# ItsyBitsy_Expander_v2_1_RP2040.net
KiCad netlist of a schematic drawn in EAGLE
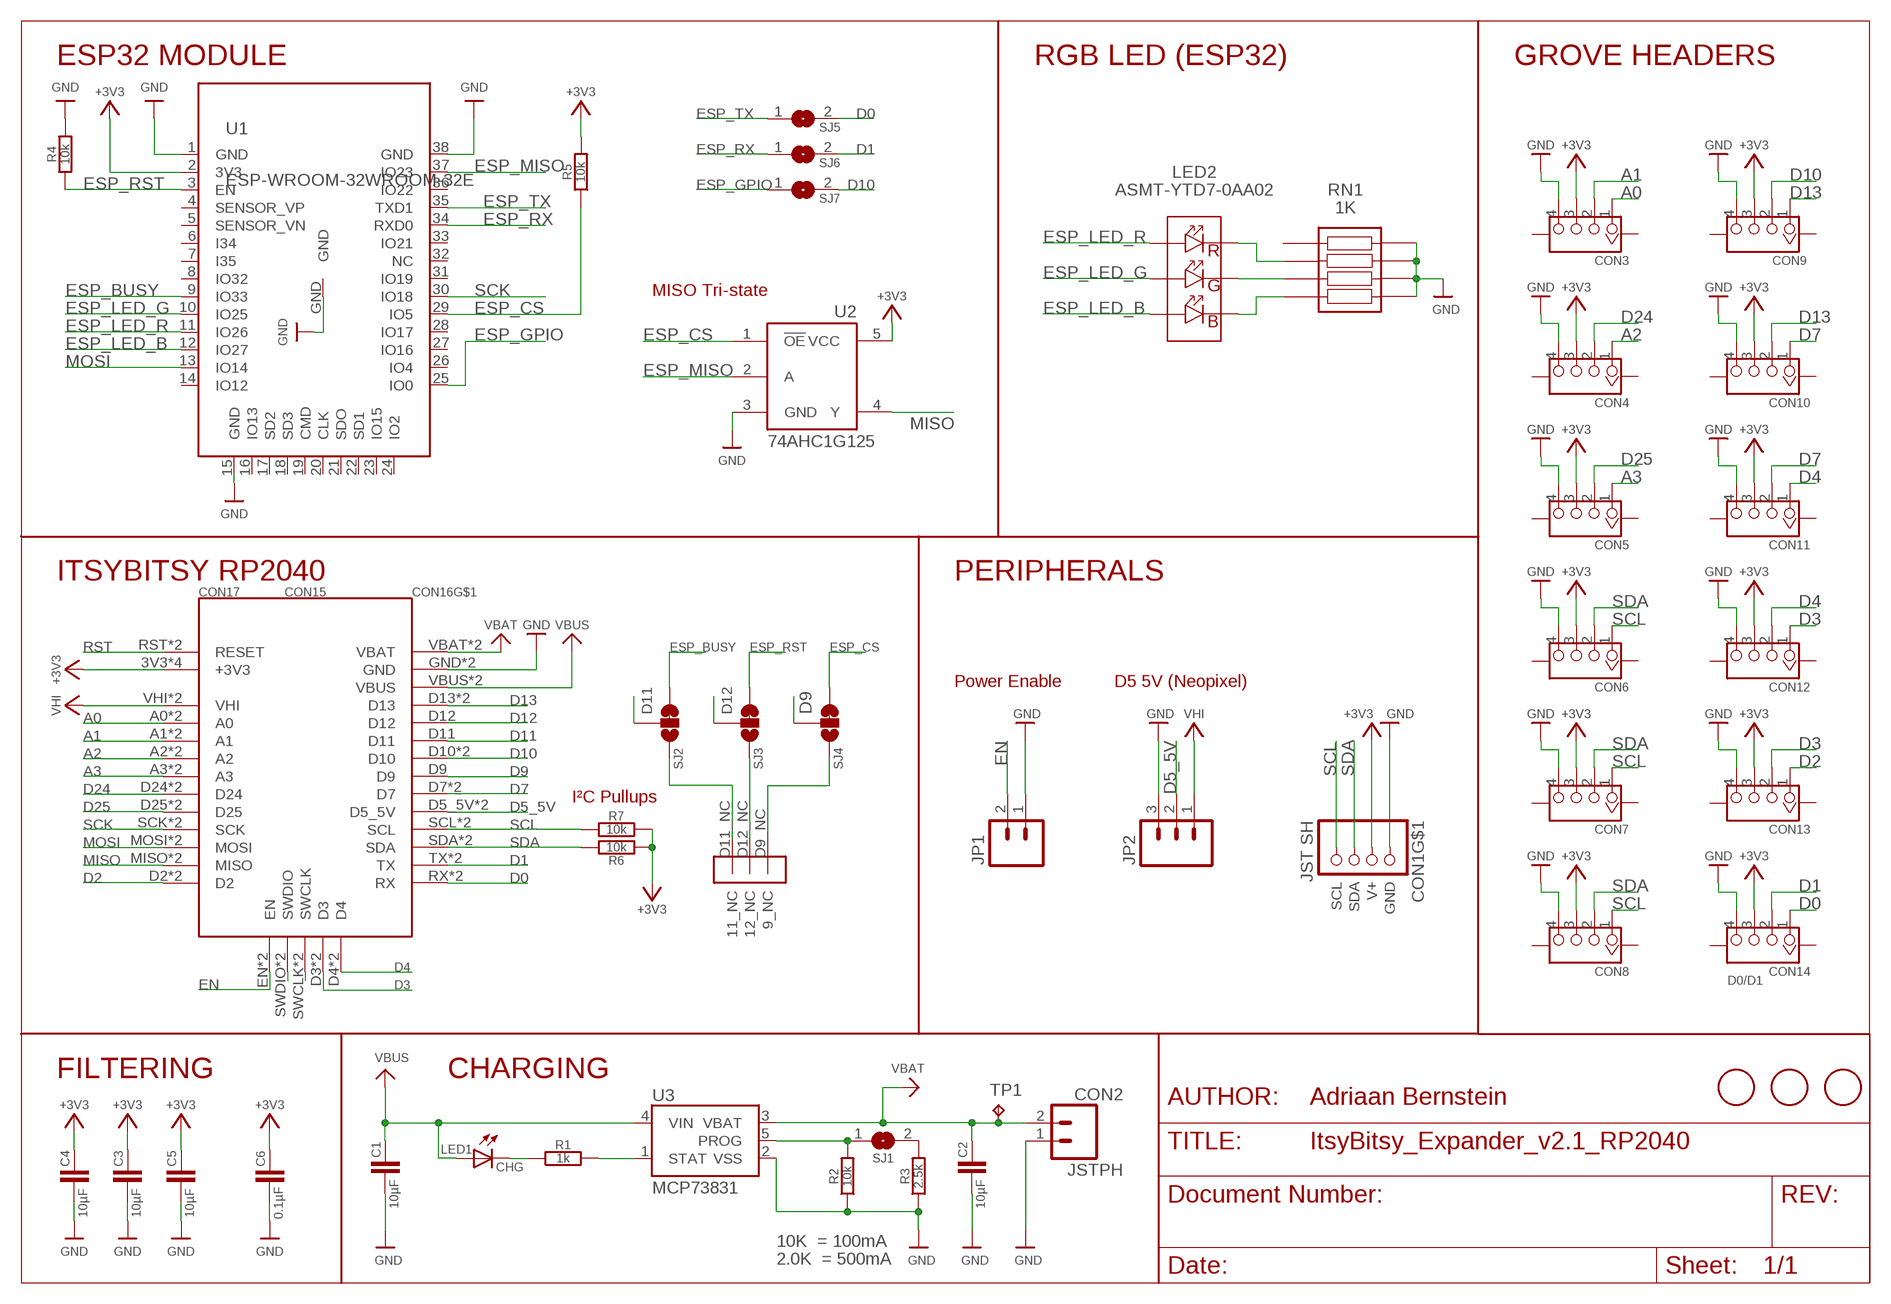
[diagram p0: schematic, sheet 1]

(export (version "E")
  (design (tool "Eeschema 10.0.6"))
  (components
    (comp (ref "C1")
      (value "10µF")
      (footprint "eagle-import:C0805")
      (libsource (lib "eagle-import") (part "C-EUC0805"))
    )
    (comp (ref "C2")
      (value "10µF")
      (footprint "eagle-import:C0805")
      (libsource (lib "eagle-import") (part "C-EUC0805"))
    )
    (comp (ref "C3")
      (value "10µF")
      (footprint "eagle-import:C0805")
      (libsource (lib "eagle-import") (part "C-EUC0805"))
    )
    (comp (ref "C4")
      (value "10µF")
      (footprint "eagle-import:C0805")
      (libsource (lib "eagle-import") (part "C-EUC0805"))
    )
    (comp (ref "C5")
      (value "10µF")
      (footprint "eagle-import:C0805")
      (libsource (lib "eagle-import") (part "C-EUC0805"))
    )
    (comp (ref "C6")
      (value "0.1µF")
      (footprint "eagle-import:C0805")
      (libsource (lib "eagle-import") (part "C-EUC0805"))
    )
    (comp (ref "CON1")
      (value "JST SH")
      (footprint "eagle-import:JST_SH4")
      (libsource (lib "eagle-import") (part "STEMMA_I2C_QT"))
    )
    (comp (ref "CON2")
      (value "JSTPH")
      (footprint "eagle-import:JST-2-SMD")
      (libsource (lib "eagle-import") (part "M02-JST-2MM-SMT"))
    )
    (comp (ref "CON3")
      (value "H4P-SMD-2.0")
      (footprint "eagle-import:HW4-PTH-2.0")
      (libsource (lib "eagle-import") (part "GROVE-CONNECTOR-4PINHW4-PTH-2.0"))
    )
    (comp (ref "CON4")
      (value "H4P-SMD-2.0")
      (footprint "eagle-import:HW4-PTH-2.0")
      (libsource (lib "eagle-import") (part "GROVE-CONNECTOR-4PINHW4-PTH-2.0"))
    )
    (comp (ref "CON5")
      (value "H4P-SMD-2.0")
      (footprint "eagle-import:HW4-PTH-2.0")
      (libsource (lib "eagle-import") (part "GROVE-CONNECTOR-4PINHW4-PTH-2.0"))
    )
    (comp (ref "CON6")
      (value "H4P-SMD-2.0")
      (footprint "eagle-import:HW4-PTH-2.0")
      (libsource (lib "eagle-import") (part "GROVE-CONNECTOR-4PINHW4-PTH-2.0"))
    )
    (comp (ref "CON7")
      (value "H4P-SMD-2.0")
      (footprint "eagle-import:HW4-PTH-2.0")
      (libsource (lib "eagle-import") (part "GROVE-CONNECTOR-4PINHW4-PTH-2.0"))
    )
    (comp (ref "CON8")
      (value "H4P-SMD-2.0")
      (footprint "eagle-import:HW4-PTH-2.0")
      (libsource (lib "eagle-import") (part "GROVE-CONNECTOR-4PINHW4-PTH-2.0"))
    )
    (comp (ref "CON9")
      (value "H4P-SMD-2.0")
      (footprint "eagle-import:HW4-PTH-2.0")
      (libsource (lib "eagle-import") (part "GROVE-CONNECTOR-4PINHW4-PTH-2.0"))
    )
    (comp (ref "CON10")
      (value "H4P-SMD-2.0")
      (footprint "eagle-import:HW4-PTH-2.0")
      (libsource (lib "eagle-import") (part "GROVE-CONNECTOR-4PINHW4-PTH-2.0"))
    )
    (comp (ref "CON11")
      (value "H4P-SMD-2.0")
      (footprint "eagle-import:HW4-PTH-2.0")
      (libsource (lib "eagle-import") (part "GROVE-CONNECTOR-4PINHW4-PTH-2.0"))
    )
    (comp (ref "CON12")
      (value "H4P-SMD-2.0")
      (footprint "eagle-import:HW4-PTH-2.0")
      (libsource (lib "eagle-import") (part "GROVE-CONNECTOR-4PINHW4-PTH-2.0"))
    )
    (comp (ref "CON13")
      (value "H4P-SMD-2.0")
      (footprint "eagle-import:HW4-PTH-2.0")
      (libsource (lib "eagle-import") (part "GROVE-CONNECTOR-4PINHW4-PTH-2.0"))
    )
    (comp (ref "CON14")
      (value "H4P-SMD-2.0")
      (footprint "eagle-import:HW4-PTH-2.0")
      (libsource (lib "eagle-import") (part "GROVE-CONNECTOR-4PINHW4-PTH-2.0"))
    )
    (comp (ref "CON15")
      (value "ITSYBITSY_RP2040_EDGEDEBUG")
      (footprint "eagle-import:ITSYBITSY_RP2040_PTH_EDGEDEBUG")
      (libsource (lib "eagle-import") (part "ITSYBITSY_RP2040_EDGEDEBUG"))
    )
    (comp (ref "CON16")
      (value "ITSYBITSY_RP2040_EDGEGND")
      (footprint "eagle-import:ITSYBITSY_RP2040_SMD_EDGEGND")
      (libsource (lib "eagle-import") (part "ITSYBITSY_RP2040_EDGEGND"))
    )
    (comp (ref "CON17")
      (value "ITSYBITSY_RP2040_EDGEPWR")
      (footprint "eagle-import:ITSYBITSY_RP2040_SMD_EDGEPWR")
      (libsource (lib "eagle-import") (part "ITSYBITSY_RP2040_EDGEPWR"))
    )
    (comp (ref "FD1")
      (value "FIDUCIAL")
      (footprint "eagle-import:FIDUCIAL_1MM")
      (libsource (lib "eagle-import") (part "FIDUCIAL"))
    )
    (comp (ref "FD2")
      (value "FIDUCIAL")
      (footprint "eagle-import:FIDUCIAL_1MM")
      (libsource (lib "eagle-import") (part "FIDUCIAL"))
    )
    (comp (ref "FD3")
      (value "FIDUCIAL")
      (footprint "eagle-import:FIDUCIAL_1MM")
      (libsource (lib "eagle-import") (part "FIDUCIAL"))
    )
    (comp (ref "JP1")
      (value "M02PTH")
      (footprint "eagle-import:1X02")
      (libsource (lib "eagle-import") (part "M02PTH"))
    )
    (comp (ref "JP2")
      (value "M03PTH")
      (footprint "eagle-import:1X03")
      (libsource (lib "eagle-import") (part "M03PTH"))
    )
    (comp (ref "LED1")
      (value "CHG")
      (footprint "eagle-import:CHIP-LED0603")
      (libsource (lib "eagle-import") (part "LEDCHIP-LED0603"))
    )
    (comp (ref "LED2")
      (value "ASMT-YTD7-0AA02")
      (footprint "eagle-import:ASMTYTD70AA02")
      (fields (field (name "MOUSER_PART_NUMBER") "630-ASMT-YTD7-0AA02"))
      (libsource (lib "eagle-import") (part "ASMT-YTD7-0AA02"))
    )
    (comp (ref "R1")
      (value "1k")
      (footprint "eagle-import:R0603")
      (libsource (lib "eagle-import") (part "R-EU_R0603"))
    )
    (comp (ref "R2")
      (value "10k")
      (footprint "eagle-import:R0603")
      (libsource (lib "eagle-import") (part "R-EU_R0603"))
    )
    (comp (ref "R3")
      (value "2.5k")
      (footprint "eagle-import:R0603")
      (libsource (lib "eagle-import") (part "R-EU_R0603"))
    )
    (comp (ref "R4")
      (value "10k")
      (footprint "eagle-import:R0603")
      (libsource (lib "eagle-import") (part "R-EU_R0603"))
    )
    (comp (ref "R5")
      (value "10k")
      (footprint "eagle-import:R0603")
      (libsource (lib "eagle-import") (part "R-EU_R0603"))
    )
    (comp (ref "R6")
      (value "10k")
      (footprint "eagle-import:R0603")
      (libsource (lib "eagle-import") (part "R-EU_R0603"))
    )
    (comp (ref "R7")
      (value "10k")
      (footprint "eagle-import:R0603")
      (libsource (lib "eagle-import") (part "R-EU_R0603"))
    )
    (comp (ref "RN1")
      (value "1K")
      (footprint "eagle-import:CAY1647R0F4LF")
      (fields
        (field (name "MANUFACTURER_PART_NUMBER") "CAY16-221J4AS")
        (field (name "MOUSER_PART_NUMBER") "652-CAY16-221J4AS")
      )
      (libsource (lib "eagle-import") (part "CAY16-221J4AS"))
    )
    (comp (ref "SJ1") (value "SJ") (footprint "eagle-import:SJ") (libsource (lib "eagle-import") (part "SJ")))
    (comp (ref "SJ5") (value "SJ") (footprint "eagle-import:SJ") (libsource (lib "eagle-import") (part "SJ")))
    (comp (ref "SJ6") (value "SJ") (footprint "eagle-import:SJ") (libsource (lib "eagle-import") (part "SJ")))
    (comp (ref "SJ7") (value "SJ") (footprint "eagle-import:SJ") (libsource (lib "eagle-import") (part "SJ")))
    (comp (ref "SJ_D11")
      (value "SJ2")
      (footprint "eagle-import:SJ_2WAY_CLOSED")
      (libsource (lib "eagle-import") (part "SJ_2WAY_CLOSED"))
    )
    (comp (ref "SJ_D12")
      (value "SJ3")
      (footprint "eagle-import:SJ_2WAY_CLOSED")
      (libsource (lib "eagle-import") (part "SJ_2WAY_CLOSED"))
    )
    (comp (ref "SJ_D13")
      (value "SJ4")
      (footprint "eagle-import:SJ_2WAY_CLOSED")
      (libsource (lib "eagle-import") (part "SJ_2WAY_CLOSED"))
    )
    (comp (ref "TP1")
      (value "TPB1,27")
      (footprint "eagle-import:B1,27")
      (libsource (lib "eagle-import") (part "TPB1,27"))
    )
    (comp (ref "U1")
      (value "ESP-WROOM-32WROOM-32E")
      (footprint "eagle-import:ESP-WROOM-32E")
      (libsource (lib "eagle-import") (part "ESP-WROOM-32WROOM-32E"))
    )
    (comp (ref "U2")
      (value "74AHC1G125")
      (footprint "eagle-import:SOT23-5L")
      (libsource (lib "eagle-import") (part "74AHC1G125"))
    )
    (comp (ref "U3")
      (value "MCP73831")
      (footprint "eagle-import:SOT23-5")
      (libsource (lib "eagle-import") (part "MCP73831"))
    )
  )
  (nets
    (net (code "1") (name "+3V3") (class "Default")
      (node (ref "C3") (pin "1") (pinfunction "1_1") (pintype "passive"))
      (node (ref "C4") (pin "1") (pinfunction "1_1") (pintype "passive"))
      (node (ref "C5") (pin "1") (pinfunction "1_1") (pintype "passive"))
      (node (ref "C6") (pin "1") (pinfunction "1_1") (pintype "passive"))
      (node (ref "CON1") (pin "2") (pinfunction "V+_2") (pintype "passive"))
      (node (ref "CON10") (pin "3") (pinfunction "3_3") (pintype "bidirectional"))
      (node (ref "CON11") (pin "3") (pinfunction "3_3") (pintype "bidirectional"))
      (node (ref "CON12") (pin "3") (pinfunction "3_3") (pintype "bidirectional"))
      (node (ref "CON13") (pin "3") (pinfunction "3_3") (pintype "bidirectional"))
      (node (ref "CON14") (pin "3") (pinfunction "3_3") (pintype "bidirectional"))
      (node (ref "CON17") (pin "3V3") (pinfunction "+3V3_3V3") (pintype "bidirectional"))
      (node (ref "CON17") (pin "3V3_2") (pinfunction "+3V3_3V3_2") (pintype "bidirectional"))
      (node (ref "CON17") (pin "3V3_3") (pinfunction "+3V3_3V3_3") (pintype "bidirectional"))
      (node (ref "CON17") (pin "3V3_4") (pinfunction "+3V3_3V3_4") (pintype "bidirectional"))
      (node (ref "CON3") (pin "3") (pinfunction "3_3") (pintype "bidirectional"))
      (node (ref "CON4") (pin "3") (pinfunction "3_3") (pintype "bidirectional"))
      (node (ref "CON5") (pin "3") (pinfunction "3_3") (pintype "bidirectional"))
      (node (ref "CON6") (pin "3") (pinfunction "3_3") (pintype "bidirectional"))
      (node (ref "CON7") (pin "3") (pinfunction "3_3") (pintype "bidirectional"))
      (node (ref "CON8") (pin "3") (pinfunction "3_3") (pintype "bidirectional"))
      (node (ref "CON9") (pin "3") (pinfunction "3_3") (pintype "bidirectional"))
      (node (ref "R5") (pin "2") (pinfunction "2_2") (pintype "passive"))
      (node (ref "R6") (pin "1") (pinfunction "1_1") (pintype "passive"))
      (node (ref "R7") (pin "1") (pinfunction "1_1") (pintype "passive"))
      (node (ref "U1") (pin "2") (pinfunction "3V3_2") (pintype "bidirectional"))
      (node (ref "U2") (pin "5") (pinfunction "VCC_5") (pintype "power_in"))
    )
    (net (code "2") (name "/A0") (class "Default")
      (node (ref "CON17") (pin "A0") (pinfunction "A0_A0") (pintype "bidirectional"))
      (node (ref "CON17") (pin "A0_2") (pinfunction "A0_A0_2") (pintype "bidirectional"))
      (node (ref "CON3") (pin "1") (pinfunction "1_1") (pintype "bidirectional"))
    )
    (net (code "3") (name "/A1") (class "Default")
      (node (ref "CON17") (pin "A1") (pinfunction "A1_A1") (pintype "bidirectional"))
      (node (ref "CON17") (pin "A1_2") (pinfunction "A1_A1_2") (pintype "bidirectional"))
      (node (ref "CON3") (pin "2") (pinfunction "2_2") (pintype "bidirectional"))
    )
    (net (code "4") (name "/A2") (class "Default")
      (node (ref "CON17") (pin "A2") (pinfunction "A2_A2") (pintype "bidirectional"))
      (node (ref "CON17") (pin "A2_2") (pinfunction "A2_A2_2") (pintype "bidirectional"))
      (node (ref "CON4") (pin "1") (pinfunction "1_1") (pintype "bidirectional"))
    )
    (net (code "5") (name "/A3") (class "Default")
      (node (ref "CON17") (pin "A3") (pinfunction "A3_A3") (pintype "bidirectional"))
      (node (ref "CON17") (pin "A3_2") (pinfunction "A3_A3_2") (pintype "bidirectional"))
      (node (ref "CON5") (pin "1") (pinfunction "1_1") (pintype "bidirectional"))
    )
    (net (code "6") (name "/D0") (class "Default")
      (node (ref "CON14") (pin "1") (pinfunction "1_1") (pintype "bidirectional"))
      (node (ref "CON15") (pin "RX") (pinfunction "RX_RX") (pintype "bidirectional"))
      (node (ref "CON15") (pin "RX_2") (pinfunction "RX_RX_2") (pintype "bidirectional"))
      (node (ref "SJ5") (pin "2") (pinfunction "2_2") (pintype "passive"))
    )
    (net (code "7") (name "/D1") (class "Default")
      (node (ref "CON14") (pin "2") (pinfunction "2_2") (pintype "bidirectional"))
      (node (ref "CON16") (pin "TX") (pinfunction "TX_TX") (pintype "bidirectional"))
      (node (ref "CON16") (pin "TX_2") (pinfunction "TX_TX_2") (pintype "bidirectional"))
      (node (ref "SJ6") (pin "2") (pinfunction "2_2") (pintype "passive"))
    )
    (net (code "8") (name "/D2") (class "Default")
      (node (ref "CON13") (pin "1") (pinfunction "1_1") (pintype "bidirectional"))
      (node (ref "CON15") (pin "D2") (pinfunction "D2_D2") (pintype "bidirectional"))
      (node (ref "CON15") (pin "D2_2") (pinfunction "D2_D2_2") (pintype "bidirectional"))
    )
    (net (code "9") (name "/D3") (class "Default")
      (node (ref "CON12") (pin "1") (pinfunction "1_1") (pintype "bidirectional"))
      (node (ref "CON13") (pin "2") (pinfunction "2_2") (pintype "bidirectional"))
      (node (ref "CON15") (pin "D3") (pinfunction "D3_D3") (pintype "bidirectional"))
      (node (ref "CON15") (pin "D3_2") (pinfunction "D3_D3_2") (pintype "bidirectional"))
    )
    (net (code "10") (name "/D4") (class "Default")
      (node (ref "CON11") (pin "1") (pinfunction "1_1") (pintype "bidirectional"))
      (node (ref "CON12") (pin "2") (pinfunction "2_2") (pintype "bidirectional"))
      (node (ref "CON15") (pin "D4") (pinfunction "D4_D4") (pintype "bidirectional"))
      (node (ref "CON15") (pin "D4_2") (pinfunction "D4_D4_2") (pintype "bidirectional"))
    )
    (net (code "11") (name "/D5_5V") (class "Default")
      (node (ref "CON16") (pin "D5_5V") (pinfunction "D5_5V_D5_5V") (pintype "bidirectional"))
      (node (ref "CON16") (pin "D5_5V_2") (pinfunction "D5_5V_D5_5V_2") (pintype "bidirectional"))
      (node (ref "JP2") (pin "2") (pinfunction "2_2") (pintype "passive"))
    )
    (net (code "12") (name "/D7") (class "Default")
      (node (ref "CON10") (pin "1") (pinfunction "1_1") (pintype "bidirectional"))
      (node (ref "CON11") (pin "2") (pinfunction "2_2") (pintype "bidirectional"))
      (node (ref "CON16") (pin "D7") (pinfunction "D7_D7") (pintype "bidirectional"))
      (node (ref "CON16") (pin "D7_2") (pinfunction "D7_D7_2") (pintype "bidirectional"))
    )
    (net (code "13") (name "/D9") (class "Default")
      (node (ref "CON16") (pin "D9") (pinfunction "D9_D9") (pintype "bidirectional"))
      (node (ref "SJ_D13") (pin "2") (pinfunction "2_2") (pintype "passive"))
    )
    (net (code "14") (name "/D10") (class "Default")
      (node (ref "CON16") (pin "D10") (pinfunction "D10_D10") (pintype "bidirectional"))
      (node (ref "CON16") (pin "D10_2") (pinfunction "D10_D10_2") (pintype "bidirectional"))
      (node (ref "CON9") (pin "2") (pinfunction "2_2") (pintype "bidirectional"))
      (node (ref "SJ7") (pin "2") (pinfunction "2_2") (pintype "passive"))
    )
    (net (code "15") (name "/D11") (class "Default")
      (node (ref "CON16") (pin "D11") (pinfunction "D11_D11") (pintype "bidirectional"))
      (node (ref "SJ_D11") (pin "2") (pinfunction "2_2") (pintype "passive"))
    )
    (net (code "16") (name "/D12") (class "Default")
      (node (ref "CON16") (pin "D12") (pinfunction "D12_D12") (pintype "bidirectional"))
      (node (ref "SJ_D12") (pin "2") (pinfunction "2_2") (pintype "passive"))
    )
    (net (code "17") (name "/D13") (class "Default")
      (node (ref "CON10") (pin "2") (pinfunction "2_2") (pintype "bidirectional"))
      (node (ref "CON16") (pin "D13") (pinfunction "D13_D13") (pintype "bidirectional"))
      (node (ref "CON16") (pin "D13_2") (pinfunction "D13_D13_2") (pintype "bidirectional"))
      (node (ref "CON9") (pin "1") (pinfunction "1_1") (pintype "bidirectional"))
    )
    (net (code "18") (name "/D24") (class "Default")
      (node (ref "CON17") (pin "D24") (pinfunction "D24_D24") (pintype "bidirectional"))
      (node (ref "CON17") (pin "D24_2") (pinfunction "D24_D24_2") (pintype "bidirectional"))
      (node (ref "CON4") (pin "2") (pinfunction "2_2") (pintype "bidirectional"))
    )
    (net (code "19") (name "/D25") (class "Default")
      (node (ref "CON17") (pin "D25") (pinfunction "D25_D25") (pintype "bidirectional"))
      (node (ref "CON17") (pin "D25_2") (pinfunction "D25_D25_2") (pintype "bidirectional"))
      (node (ref "CON5") (pin "2") (pinfunction "2_2") (pintype "bidirectional"))
    )
    (net (code "20") (name "/EN") (class "Default")
      (node (ref "CON15") (pin "EN") (pinfunction "EN_EN") (pintype "bidirectional"))
      (node (ref "CON15") (pin "EN_2") (pinfunction "EN_EN_2") (pintype "bidirectional"))
      (node (ref "JP1") (pin "2") (pinfunction "2_2") (pintype "passive"))
    )
    (net (code "21") (name "/ESP_BUSY") (class "Default")
      (node (ref "SJ_D11") (pin "1") (pinfunction "1_1") (pintype "passive"))
      (node (ref "U1") (pin "9") (pinfunction "IO33_9") (pintype "bidirectional"))
    )
    (net (code "22") (name "/ESP_CS") (class "Default")
      (node (ref "R5") (pin "1") (pinfunction "1_1") (pintype "passive"))
      (node (ref "SJ_D13") (pin "1") (pinfunction "1_1") (pintype "passive"))
      (node (ref "U1") (pin "29") (pinfunction "IO5_29") (pintype "bidirectional"))
      (node (ref "U2") (pin "1") (pinfunction "~{OE}_1") (pintype "input"))
    )
    (net (code "23") (name "/ESP_GPIO") (class "Default")
      (node (ref "SJ7") (pin "1") (pinfunction "1_1") (pintype "passive"))
      (node (ref "U1") (pin "25") (pinfunction "IO0_25") (pintype "bidirectional"))
    )
    (net (code "24") (name "/ESP_LED_B") (class "Default")
      (node (ref "LED2") (pin "6") (pinfunction "A_BLUE_6") (pintype "bidirectional"))
      (node (ref "U1") (pin "12") (pinfunction "IO27_12") (pintype "bidirectional"))
    )
    (net (code "25") (name "/ESP_LED_G") (class "Default")
      (node (ref "LED2") (pin "5") (pinfunction "A_GREEN_5") (pintype "bidirectional"))
      (node (ref "U1") (pin "10") (pinfunction "IO25_10") (pintype "bidirectional"))
    )
    (net (code "26") (name "/ESP_LED_R") (class "Default")
      (node (ref "LED2") (pin "4") (pinfunction "A_RED_4") (pintype "bidirectional"))
      (node (ref "U1") (pin "11") (pinfunction "IO26_11") (pintype "bidirectional"))
    )
    (net (code "27") (name "/ESP_MISO") (class "Default")
      (node (ref "U1") (pin "37") (pinfunction "IO23_37") (pintype "bidirectional"))
      (node (ref "U2") (pin "2") (pinfunction "A_2") (pintype "input"))
    )
    (net (code "28") (name "/ESP_RST") (class "Default")
      (node (ref "R4") (pin "1") (pinfunction "1_1") (pintype "passive"))
      (node (ref "SJ_D12") (pin "1") (pinfunction "1_1") (pintype "passive"))
      (node (ref "U1") (pin "3") (pinfunction "EN_3") (pintype "bidirectional"))
    )
    (net (code "29") (name "/ESP_RX") (class "Default")
      (node (ref "SJ6") (pin "1") (pinfunction "1_1") (pintype "passive"))
      (node (ref "U1") (pin "34") (pinfunction "RXD0_34") (pintype "bidirectional"))
    )
    (net (code "30") (name "/ESP_TX") (class "Default")
      (node (ref "SJ5") (pin "1") (pinfunction "1_1") (pintype "passive"))
      (node (ref "U1") (pin "35") (pinfunction "TXD1_35") (pintype "bidirectional"))
    )
    (net (code "31") (name "/MISO") (class "Default")
      (node (ref "CON17") (pin "MISO") (pinfunction "MISO_MISO") (pintype "bidirectional"))
      (node (ref "CON17") (pin "MISO_2") (pinfunction "MISO_MISO_2") (pintype "bidirectional"))
      (node (ref "U2") (pin "4") (pinfunction "Y_4") (pintype "output"))
    )
    (net (code "32") (name "/MOSI") (class "Default")
      (node (ref "CON17") (pin "MOSI") (pinfunction "MOSI_MOSI") (pintype "bidirectional"))
      (node (ref "CON17") (pin "MOSI_2") (pinfunction "MOSI_MOSI_2") (pintype "bidirectional"))
      (node (ref "U1") (pin "13") (pinfunction "IO14_13") (pintype "bidirectional"))
    )
    (net (code "33") (name "/RST") (class "Default")
      (node (ref "CON17") (pin "RST") (pinfunction "RESET_RST") (pintype "bidirectional"))
      (node (ref "CON17") (pin "RST_2") (pinfunction "RESET_RST_2") (pintype "bidirectional"))
    )
    (net (code "34") (name "/SCK") (class "Default")
      (node (ref "CON17") (pin "SCK") (pinfunction "SCK_SCK") (pintype "bidirectional"))
      (node (ref "CON17") (pin "SCK_2") (pinfunction "SCK_SCK_2") (pintype "bidirectional"))
      (node (ref "U1") (pin "30") (pinfunction "IO18_30") (pintype "bidirectional"))
    )
    (net (code "35") (name "/SCL") (class "Default")
      (node (ref "CON1") (pin "4") (pinfunction "SCL_4") (pintype "passive"))
      (node (ref "CON16") (pin "SCL") (pinfunction "SCL_SCL") (pintype "bidirectional"))
      (node (ref "CON16") (pin "SCL_2") (pinfunction "SCL_SCL_2") (pintype "bidirectional"))
      (node (ref "CON6") (pin "1") (pinfunction "1_1") (pintype "bidirectional"))
      (node (ref "CON7") (pin "1") (pinfunction "1_1") (pintype "bidirectional"))
      (node (ref "CON8") (pin "1") (pinfunction "1_1") (pintype "bidirectional"))
      (node (ref "R7") (pin "2") (pinfunction "2_2") (pintype "passive"))
    )
    (net (code "36") (name "/SDA") (class "Default")
      (node (ref "CON1") (pin "3") (pinfunction "SDA_3") (pintype "passive"))
      (node (ref "CON16") (pin "SDA") (pinfunction "SDA_SDA") (pintype "bidirectional"))
      (node (ref "CON16") (pin "SDA_2") (pinfunction "SDA_SDA_2") (pintype "bidirectional"))
      (node (ref "CON6") (pin "2") (pinfunction "2_2") (pintype "bidirectional"))
      (node (ref "CON7") (pin "2") (pinfunction "2_2") (pintype "bidirectional"))
      (node (ref "CON8") (pin "2") (pinfunction "2_2") (pintype "bidirectional"))
      (node (ref "R6") (pin "2") (pinfunction "2_2") (pintype "passive"))
    )
    (net (code "37") (name "GND") (class "Default")
      (node (ref "C1") (pin "2") (pinfunction "2_2") (pintype "passive"))
      (node (ref "C2") (pin "2") (pinfunction "2_2") (pintype "passive"))
      (node (ref "C3") (pin "2") (pinfunction "2_2") (pintype "passive"))
      (node (ref "C4") (pin "2") (pinfunction "2_2") (pintype "passive"))
      (node (ref "C5") (pin "2") (pinfunction "2_2") (pintype "passive"))
      (node (ref "C6") (pin "2") (pinfunction "2_2") (pintype "passive"))
      (node (ref "CON1") (pin "1") (pinfunction "GND_1") (pintype "passive"))
      (node (ref "CON10") (pin "4") (pinfunction "4_4") (pintype "bidirectional"))
      (node (ref "CON11") (pin "4") (pinfunction "4_4") (pintype "bidirectional"))
      (node (ref "CON12") (pin "4") (pinfunction "4_4") (pintype "bidirectional"))
      (node (ref "CON13") (pin "4") (pinfunction "4_4") (pintype "bidirectional"))
      (node (ref "CON14") (pin "4") (pinfunction "4_4") (pintype "bidirectional"))
      (node (ref "CON16") (pin "GND") (pinfunction "GND_GND") (pintype "bidirectional"))
      (node (ref "CON16") (pin "GND_2") (pinfunction "GND_GND_2") (pintype "bidirectional"))
      (node (ref "CON2") (pin "1") (pinfunction "1_1") (pintype "passive"))
      (node (ref "CON3") (pin "4") (pinfunction "4_4") (pintype "bidirectional"))
      (node (ref "CON4") (pin "4") (pinfunction "4_4") (pintype "bidirectional"))
      (node (ref "CON5") (pin "4") (pinfunction "4_4") (pintype "bidirectional"))
      (node (ref "CON6") (pin "4") (pinfunction "4_4") (pintype "bidirectional"))
      (node (ref "CON7") (pin "4") (pinfunction "4_4") (pintype "bidirectional"))
      (node (ref "CON8") (pin "4") (pinfunction "4_4") (pintype "bidirectional"))
      (node (ref "CON9") (pin "4") (pinfunction "4_4") (pintype "bidirectional"))
      (node (ref "JP1") (pin "1") (pinfunction "1_1") (pintype "passive"))
      (node (ref "JP2") (pin "3") (pinfunction "3_3") (pintype "passive"))
      (node (ref "R2") (pin "1") (pinfunction "1_1") (pintype "passive"))
      (node (ref "R3") (pin "1") (pinfunction "1_1") (pintype "passive"))
      (node (ref "R4") (pin "2") (pinfunction "2_2") (pintype "passive"))
      (node (ref "RN1") (pin "5") (pinfunction "R4_2_5") (pintype "bidirectional"))
      (node (ref "RN1") (pin "6") (pinfunction "R3_2_6") (pintype "bidirectional"))
      (node (ref "RN1") (pin "7") (pinfunction "R2_2_7") (pintype "bidirectional"))
      (node (ref "RN1") (pin "8") (pinfunction "R1_2_8") (pintype "bidirectional"))
      (node (ref "U1") (pin "1") (pinfunction "GND_1") (pintype "bidirectional"))
      (node (ref "U1") (pin "15") (pinfunction "GND_15") (pintype "bidirectional"))
      (node (ref "U1") (pin "38") (pinfunction "GND_38") (pintype "bidirectional"))
      (node (ref "U1") (pin "GND") (pinfunction "GND_GND") (pintype "bidirectional"))
      (node (ref "U2") (pin "3") (pinfunction "GND_3") (pintype "power_in"))
      (node (ref "U3") (pin "2") (pinfunction "VSS_2") (pintype "power_in"))
    )
    (net (code "38") (name "Net-(CON15-PadSWCLK)") (class "Default")
      (node (ref "CON15") (pin "SWCLK") (pinfunction "SWCLK_SWCLK") (pintype "bidirectional"))
      (node (ref "CON15") (pin "SWCLK_2") (pinfunction "SWCLK_SWCLK_2") (pintype "bidirectional"))
    )
    (net (code "39") (name "Net-(CON15-PadSWDIO)") (class "Default")
      (node (ref "CON15") (pin "SWDIO") (pinfunction "SWDIO_SWDIO") (pintype "bidirectional"))
      (node (ref "CON15") (pin "SWDIO_2") (pinfunction "SWDIO_SWDIO_2") (pintype "bidirectional"))
    )
    (net (code "40") (name "Net-(CON16B-9_NC)") (class "Default")
      (node (ref "CON16") (pin "D9_NC") (pinfunction "9_NC_D9_NC") (pintype "bidirectional"))
      (node (ref "SJ_D13") (pin "3") (pinfunction "3_3") (pintype "passive"))
    )
    (net (code "41") (name "Net-(CON16B-11_NC)") (class "Default")
      (node (ref "CON16") (pin "D11_NC") (pinfunction "11_NC_D11_NC") (pintype "bidirectional"))
      (node (ref "SJ_D11") (pin "3") (pinfunction "3_3") (pintype "passive"))
    )
    (net (code "42") (name "Net-(CON16B-12_NC)") (class "Default")
      (node (ref "CON16") (pin "D12_NC") (pinfunction "12_NC_D12_NC") (pintype "bidirectional"))
      (node (ref "SJ_D12") (pin "3") (pinfunction "3_3") (pintype "passive"))
    )
    (net (code "43") (name "Net-(LED1-PadC)") (class "Default")
      (node (ref "LED1") (pin "C") (pinfunction "C_C") (pintype "passive"))
      (node (ref "R1") (pin "1") (pinfunction "1_1") (pintype "passive"))
    )
    (net (code "44") (name "Net-(LED2-K_BLUE)") (class "Default")
      (node (ref "LED2") (pin "1") (pinfunction "K_BLUE_1") (pintype "bidirectional"))
      (node (ref "RN1") (pin "4") (pinfunction "R4_1_4") (pintype "bidirectional"))
    )
    (net (code "45") (name "Net-(LED2-K_GREEN)") (class "Default")
      (node (ref "LED2") (pin "2") (pinfunction "K_GREEN_2") (pintype "bidirectional"))
      (node (ref "RN1") (pin "3") (pinfunction "R3_1_3") (pintype "bidirectional"))
    )
    (net (code "46") (name "Net-(LED2-K_RED)") (class "Default")
      (node (ref "LED2") (pin "3") (pinfunction "K_RED_3") (pintype "bidirectional"))
      (node (ref "RN1") (pin "2") (pinfunction "R2_1_2") (pintype "bidirectional"))
    )
    (net (code "47") (name "Net-(R3-Pad2)") (class "Default")
      (node (ref "R3") (pin "2") (pinfunction "2_2") (pintype "passive"))
      (node (ref "SJ1") (pin "2") (pinfunction "2_2") (pintype "passive"))
    )
    (net (code "48") (name "Net-(U3-PROG)") (class "Default")
      (node (ref "R2") (pin "2") (pinfunction "2_2") (pintype "passive"))
      (node (ref "SJ1") (pin "1") (pinfunction "1_1") (pintype "passive"))
      (node (ref "U3") (pin "5") (pinfunction "PROG_5") (pintype "input"))
    )
    (net (code "49") (name "Net-(U3-STAT)") (class "Default")
      (node (ref "R1") (pin "2") (pinfunction "2_2") (pintype "passive"))
      (node (ref "U3") (pin "1") (pinfunction "STAT_1") (pintype "output"))
    )
    (net (code "50") (name "VBAT") (class "Default")
      (node (ref "C2") (pin "1") (pinfunction "1_1") (pintype "passive"))
      (node (ref "CON16") (pin "VBAT") (pinfunction "VBAT_VBAT") (pintype "bidirectional"))
      (node (ref "CON16") (pin "VBAT_2") (pinfunction "VBAT_VBAT_2") (pintype "bidirectional"))
      (node (ref "CON2") (pin "2") (pinfunction "2_2") (pintype "passive"))
      (node (ref "TP1") (pin "TP") (pinfunction "TP_TP") (pintype "input"))
      (node (ref "U3") (pin "3") (pinfunction "VBAT_3") (pintype "power_in"))
    )
    (net (code "51") (name "VBUS") (class "Default")
      (node (ref "C1") (pin "1") (pinfunction "1_1") (pintype "passive"))
      (node (ref "CON16") (pin "VBUS") (pinfunction "VBUS_VBUS") (pintype "bidirectional"))
      (node (ref "CON16") (pin "VBUS_2") (pinfunction "VBUS_VBUS_2") (pintype "bidirectional"))
      (node (ref "LED1") (pin "A") (pinfunction "A_A") (pintype "passive"))
      (node (ref "U3") (pin "4") (pinfunction "VIN_4") (pintype "power_in"))
    )
    (net (code "52") (name "VHI") (class "Default")
      (node (ref "CON17") (pin "VHI") (pinfunction "VHI_VHI") (pintype "bidirectional"))
      (node (ref "CON17") (pin "VHI_2") (pinfunction "VHI_VHI_2") (pintype "bidirectional"))
      (node (ref "JP2") (pin "1") (pinfunction "1_1") (pintype "passive"))
    )
    (net (code "53") (name "unconnected-(CON3-SS1-Pad5)") (class "Default")
      (node (ref "CON3") (pin "5") (pinfunction "SS1_5") (pintype "bidirectional"))
    )
    (net (code "54") (name "unconnected-(CON3-SS2-Pad6)") (class "Default")
      (node (ref "CON3") (pin "6") (pinfunction "SS2_6") (pintype "bidirectional"))
    )
    (net (code "55") (name "unconnected-(CON4-SS1-Pad5)") (class "Default")
      (node (ref "CON4") (pin "5") (pinfunction "SS1_5") (pintype "bidirectional"))
    )
    (net (code "56") (name "unconnected-(CON4-SS2-Pad6)") (class "Default")
      (node (ref "CON4") (pin "6") (pinfunction "SS2_6") (pintype "bidirectional"))
    )
    (net (code "57") (name "unconnected-(CON5-SS1-Pad5)") (class "Default")
      (node (ref "CON5") (pin "5") (pinfunction "SS1_5") (pintype "bidirectional"))
    )
    (net (code "58") (name "unconnected-(CON5-SS2-Pad6)") (class "Default")
      (node (ref "CON5") (pin "6") (pinfunction "SS2_6") (pintype "bidirectional"))
    )
    (net (code "59") (name "unconnected-(CON6-SS1-Pad5)") (class "Default")
      (node (ref "CON6") (pin "5") (pinfunction "SS1_5") (pintype "bidirectional"))
    )
    (net (code "60") (name "unconnected-(CON6-SS2-Pad6)") (class "Default")
      (node (ref "CON6") (pin "6") (pinfunction "SS2_6") (pintype "bidirectional"))
    )
    (net (code "61") (name "unconnected-(CON7-SS1-Pad5)") (class "Default")
      (node (ref "CON7") (pin "5") (pinfunction "SS1_5") (pintype "bidirectional"))
    )
    (net (code "62") (name "unconnected-(CON7-SS2-Pad6)") (class "Default")
      (node (ref "CON7") (pin "6") (pinfunction "SS2_6") (pintype "bidirectional"))
    )
    (net (code "63") (name "unconnected-(CON8-SS1-Pad5)") (class "Default")
      (node (ref "CON8") (pin "5") (pinfunction "SS1_5") (pintype "bidirectional"))
    )
    (net (code "64") (name "unconnected-(CON8-SS2-Pad6)") (class "Default")
      (node (ref "CON8") (pin "6") (pinfunction "SS2_6") (pintype "bidirectional"))
    )
    (net (code "65") (name "unconnected-(CON9-SS1-Pad5)") (class "Default")
      (node (ref "CON9") (pin "5") (pinfunction "SS1_5") (pintype "bidirectional"))
    )
    (net (code "66") (name "unconnected-(CON9-SS2-Pad6)") (class "Default")
      (node (ref "CON9") (pin "6") (pinfunction "SS2_6") (pintype "bidirectional"))
    )
    (net (code "67") (name "unconnected-(CON10-SS1-Pad5)") (class "Default")
      (node (ref "CON10") (pin "5") (pinfunction "SS1_5") (pintype "bidirectional"))
    )
    (net (code "68") (name "unconnected-(CON10-SS2-Pad6)") (class "Default")
      (node (ref "CON10") (pin "6") (pinfunction "SS2_6") (pintype "bidirectional"))
    )
    (net (code "69") (name "unconnected-(CON11-SS1-Pad5)") (class "Default")
      (node (ref "CON11") (pin "5") (pinfunction "SS1_5") (pintype "bidirectional"))
    )
    (net (code "70") (name "unconnected-(CON11-SS2-Pad6)") (class "Default")
      (node (ref "CON11") (pin "6") (pinfunction "SS2_6") (pintype "bidirectional"))
    )
    (net (code "71") (name "unconnected-(CON12-SS1-Pad5)") (class "Default")
      (node (ref "CON12") (pin "5") (pinfunction "SS1_5") (pintype "bidirectional"))
    )
    (net (code "72") (name "unconnected-(CON12-SS2-Pad6)") (class "Default")
      (node (ref "CON12") (pin "6") (pinfunction "SS2_6") (pintype "bidirectional"))
    )
    (net (code "73") (name "unconnected-(CON13-SS1-Pad5)") (class "Default")
      (node (ref "CON13") (pin "5") (pinfunction "SS1_5") (pintype "bidirectional"))
    )
    (net (code "74") (name "unconnected-(CON13-SS2-Pad6)") (class "Default")
      (node (ref "CON13") (pin "6") (pinfunction "SS2_6") (pintype "bidirectional"))
    )
    (net (code "75") (name "unconnected-(CON14-SS1-Pad5)") (class "Default")
      (node (ref "CON14") (pin "5") (pinfunction "SS1_5") (pintype "bidirectional"))
    )
    (net (code "76") (name "unconnected-(CON14-SS2-Pad6)") (class "Default")
      (node (ref "CON14") (pin "6") (pinfunction "SS2_6") (pintype "bidirectional"))
    )
    (net (code "77") (name "unconnected-(RN1-R1_1-Pad1)") (class "Default")
      (node (ref "RN1") (pin "1") (pinfunction "R1_1_1") (pintype "bidirectional"))
    )
    (net (code "78") (name "unconnected-(U1-CLK-Pad20)") (class "Default")
      (node (ref "U1") (pin "20") (pinfunction "CLK_20") (pintype "bidirectional"))
    )
    (net (code "79") (name "unconnected-(U1-CMD-Pad19)") (class "Default")
      (node (ref "U1") (pin "19") (pinfunction "CMD_19") (pintype "bidirectional"))
    )
    (net (code "80") (name "unconnected-(U1-I34-Pad6)") (class "Default")
      (node (ref "U1") (pin "6") (pinfunction "I34_6") (pintype "input"))
    )
    (net (code "81") (name "unconnected-(U1-I35-Pad7)") (class "Default")
      (node (ref "U1") (pin "7") (pinfunction "I35_7") (pintype "input"))
    )
    (net (code "82") (name "unconnected-(U1-IO2-Pad24)") (class "Default")
      (node (ref "U1") (pin "24") (pinfunction "IO2_24") (pintype "bidirectional"))
    )
    (net (code "83") (name "unconnected-(U1-IO4-Pad26)") (class "Default")
      (node (ref "U1") (pin "26") (pinfunction "IO4_26") (pintype "bidirectional"))
    )
    (net (code "84") (name "unconnected-(U1-IO12-Pad14)") (class "Default")
      (node (ref "U1") (pin "14") (pinfunction "IO12_14") (pintype "bidirectional"))
    )
    (net (code "85") (name "unconnected-(U1-IO13-Pad16)") (class "Default")
      (node (ref "U1") (pin "16") (pinfunction "IO13_16") (pintype "bidirectional"))
    )
    (net (code "86") (name "unconnected-(U1-IO15-Pad23)") (class "Default")
      (node (ref "U1") (pin "23") (pinfunction "IO15_23") (pintype "bidirectional"))
    )
    (net (code "87") (name "unconnected-(U1-IO16-Pad27)") (class "Default")
      (node (ref "U1") (pin "27") (pinfunction "IO16_27") (pintype "bidirectional"))
    )
    (net (code "88") (name "unconnected-(U1-IO17-Pad28)") (class "Default")
      (node (ref "U1") (pin "28") (pinfunction "IO17_28") (pintype "bidirectional"))
    )
    (net (code "89") (name "unconnected-(U1-IO19-Pad31)") (class "Default")
      (node (ref "U1") (pin "31") (pinfunction "IO19_31") (pintype "bidirectional"))
    )
    (net (code "90") (name "unconnected-(U1-IO21-Pad33)") (class "Default")
      (node (ref "U1") (pin "33") (pinfunction "IO21_33") (pintype "bidirectional"))
    )
    (net (code "91") (name "unconnected-(U1-IO22-Pad36)") (class "Default")
      (node (ref "U1") (pin "36") (pinfunction "IO22_36") (pintype "bidirectional"))
    )
    (net (code "92") (name "unconnected-(U1-IO32-Pad8)") (class "Default")
      (node (ref "U1") (pin "8") (pinfunction "IO32_8") (pintype "bidirectional"))
    )
    (net (code "93") (name "unconnected-(U1-NC-Pad32)") (class "Default")
      (node (ref "U1") (pin "32") (pinfunction "NC_32") (pintype "bidirectional"))
    )
    (net (code "94") (name "unconnected-(U1-SD1-Pad22)") (class "Default")
      (node (ref "U1") (pin "22") (pinfunction "SD1_22") (pintype "bidirectional"))
    )
    (net (code "95") (name "unconnected-(U1-SD2-Pad17)") (class "Default")
      (node (ref "U1") (pin "17") (pinfunction "SD2_17") (pintype "bidirectional"))
    )
    (net (code "96") (name "unconnected-(U1-SD3-Pad18)") (class "Default")
      (node (ref "U1") (pin "18") (pinfunction "SD3_18") (pintype "bidirectional"))
    )
    (net (code "97") (name "unconnected-(U1-SDO-Pad21)") (class "Default")
      (node (ref "U1") (pin "21") (pinfunction "SDO_21") (pintype "bidirectional"))
    )
    (net (code "98") (name "unconnected-(U1-SENSOR_VN-Pad5)") (class "Default")
      (node (ref "U1") (pin "5") (pinfunction "SENSOR_VN_5") (pintype "input"))
    )
    (net (code "99") (name "unconnected-(U1-SENSOR_VP-Pad4)") (class "Default")
      (node (ref "U1") (pin "4") (pinfunction "SENSOR_VP_4") (pintype "input"))
    )
  )
)
